# Acondicionamiento_70Q.net
KiCad netlist of a schematic drawn in Altium Designer
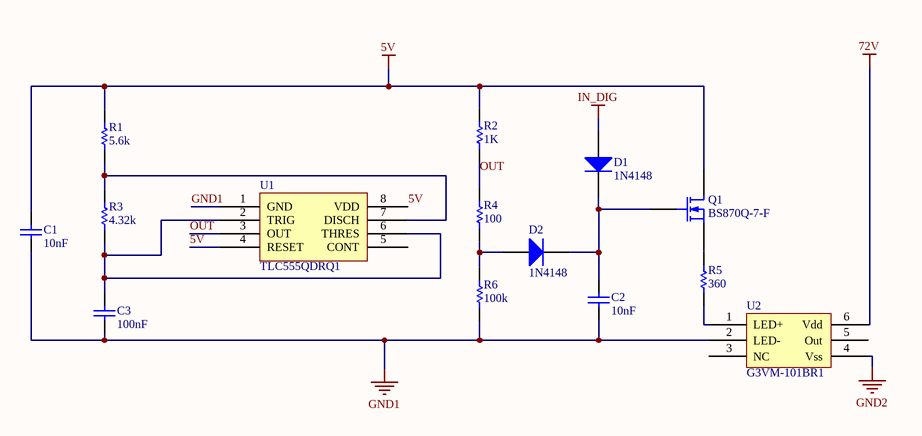
[diagram p0: Acondicionamiento_70Q.SchDoc]

(export (version "E")
  (design (tool "Eeschema 10.0.6"))
  (components
    (comp (ref "C1")
      (value "10nF")
      (footprint "C0805")
      (description "C0805C103K5RACTU - CAP, 0.01µF, 50V, 10%, X7R, 0805, REEL")
      (fields
        (field (name "MANUFACTURER") "KEMET")
        (field (name "MANUFACTURER PART NUMBER") "C0805C103K5RACTU")
      )
      (libsource (lib "Metro PA-M50") (part "CAP-10nF/50V"))
    )
    (comp (ref "C2")
      (value "10nF")
      (footprint "C0805")
      (description "C0805C103K5RACTU - CAP, 0.01µF, 50V, 10%, X7R, 0805, REEL")
      (fields
        (field (name "MANUFACTURER") "KEMET")
        (field (name "MANUFACTURER PART NUMBER") "C0805C103K5RACTU")
      )
      (libsource (lib "Metro PA-M50") (part "CAP-10nF/50V"))
    )
    (comp (ref "C3")
      (value "100nF")
      (footprint "C0805_B")
      (description "CC0805JPX7R8BB104")
      (fields
        (field (name "MANUFACTURER") "Yageo")
        (field (name "MANUFACTURER PART NUMBER") "CC1206JKX7R9BB105")
        (field (name "PUBLISHER") "Altium Limited")
      )
      (libsource (lib "Metro PA-M50") (part "CAP-0.1uF_0805_B"))
    )
    (comp (ref "D1")
      (value "1N4148")
      (footprint "SOD-323-2")
      (description "1N4148WS-HG3-08")
      (fields (field (name "MANUFACTURER") "Vishay Semiconductors"))
      (libsource (lib "Metro PA-M50") (part "DIO-1N4148"))
    )
    (comp (ref "D2")
      (value "1N4148")
      (footprint "SOD-323-2")
      (description "1N4148WS-HG3-08")
      (fields (field (name "MANUFACTURER") "Vishay Semiconductors"))
      (libsource (lib "Metro PA-M50") (part "DIO-1N4148"))
    )
    (comp (ref "Q1")
      (value "BS870Q-7-F")
      (footprint "SOT23_3")
      (description "MOSFET CHANNEL N 41V 60V SOT23")
      (fields (field (name "MANUFACTURER") "Diodes"))
      (libsource (lib "Metro PA-M50") (part "MOS_N-BS870Q-7-F"))
    )
    (comp (ref "R1")
      (value "5.6k")
      (footprint "R-0805")
      (description "PCF0805-13-5K6BT1 WELWYN  THIN FILM RESISTOR, 5.6KOHM, 100mW 0.1%")
      (fields
        (field (name "MANUFACTURER") "TT Welwyn")
        (field (name "MANUFACTURER PART NUMBER") "PCF0805-13-5K6-B-T1")
      )
      (libsource (lib "Metro PA-M50") (part "RES-5.6K/0805"))
    )
    (comp (ref "R2")
      (value "1K")
      (footprint "R-0805")
      (description "Thin Film Resistors - SMD 1Kohms .1% 25ppm")
      (fields
        (field (name "MANUFACTURER") "Vishay Sfernice")
        (field (name "MANUFACTURER PART NUMBER") "P-0805E1001BBT1")
      )
      (libsource (lib "Metro PA-M50") (part "RES-1K/0805"))
    )
    (comp (ref "R3")
      (value "4.32k")
      (footprint "R-0805")
      (description "ERA-6AEB4321V")
      (fields (field (name "TOLERANCE") "0.1%") (field (name "MANUFACTURER") "Panasonic"))
      (libsource (lib "Metro PA-M50") (part "Res-4.32k"))
    )
    (comp (ref "R4")
      (value "100")
      (footprint "R-0805")
      (description "MCU08050C1000FP500")
      (fields (field (name "MANUFACTURER") "Vishay Beyschlag") (field (name "TOLERANCE") "1%"))
      (libsource (lib "Metro PA-M50") (part "RES-100"))
    )
    (comp (ref "R5")
      (value "360")
      (footprint "R-0805")
      (description "ERJ-6ENF3600V            RESISTOR, THICK FILM, 360OHM, 125mW, ± 1%")
      (fields
        (field (name "MANUFACTURER") "Panasonic")
        (field (name "MANUFACTURER PART NUMBER") "ERJ-6ENF3600V")
      )
      (libsource (lib "Metro PA-M50") (part "RES-360"))
    )
    (comp (ref "R6")
      (value "100k")
      (footprint "R-0805")
      (description "TNPW0805100KBEEA Res Thick Film 1206 100K Ohm 1% 0.25W(1/4W) ±100ppm/C Pad SMD T/R")
      (fields
        (field (name "MANUFACTURER") "Vishay Dale")
        (field (name "MANUFACTURER PART NUMBER") "TNPW0805100KBEEA")
      )
      (libsource (lib "Metro PA-M50") (part "RES-100k/0805"))
    )
    (comp (ref "U1")
      (value "TLC555QDRQ1")
      (footprint "SOIC8")
      (description "Standard Timer Single Automotive 8-Pin SOIC T/R")
      (fields (field (name "MANUFACTURER") "Texas Instruments"))
      (libsource (lib "Metro PA-M50") (part "Timer-TLC555-Q1"))
    )
    (comp (ref "U2")
      (value "G3VM-101BR1")
      (footprint "DIP-6")
      (description "G3VM-101BR1 Mosfet Relay SPST 4A 6DIP")
      (fields (field (name "MANUFACTURER") "Omron"))
      (libsource (lib "Metro PA-M50") (part "Optoacoplador-G3VM-101BR1"))
    )
  )
  (nets
    (net (code "1") (name "/OUT") (class "Default")
      (node (ref "R2") (pin "1") (pinfunction "1_1") (pintype "passive"))
      (node (ref "R4") (pin "2") (pinfunction "2_2") (pintype "passive"))
      (node (ref "U1") (pin "3") (pinfunction "OUT_3") (pintype "passive"))
    )
    (net (code "2") (name "5V") (class "Default")
      (node (ref "C1") (pin "2") (pinfunction "2_2") (pintype "passive"))
      (node (ref "Q1") (pin "3") (pinfunction "D_3") (pintype "passive"))
      (node (ref "R1") (pin "2") (pinfunction "2_2") (pintype "passive"))
      (node (ref "R2") (pin "2") (pinfunction "2_2") (pintype "passive"))
      (node (ref "U1") (pin "4") (pinfunction "RESET_4") (pintype "passive"))
      (node (ref "U1") (pin "8") (pinfunction "VDD_8") (pintype "passive"))
    )
    (net (code "3") (name "72V") (class "Default")
      (node (ref "U2") (pin "6") (pinfunction "Vdd_6") (pintype "passive"))
    )
    (net (code "4") (name "GND1") (class "Default")
      (node (ref "C1") (pin "1") (pinfunction "1_1") (pintype "passive"))
      (node (ref "C2") (pin "1") (pinfunction "1_1") (pintype "passive"))
      (node (ref "C3") (pin "1") (pinfunction "1_1") (pintype "passive"))
      (node (ref "R6") (pin "1") (pinfunction "1_1") (pintype "passive"))
      (node (ref "U1") (pin "1") (pinfunction "GND_1") (pintype "passive"))
      (node (ref "U2") (pin "2") (pinfunction "LED-_2") (pintype "passive"))
    )
    (net (code "5") (name "GND2") (class "Default")
      (node (ref "U2") (pin "4") (pinfunction "Vss_4") (pintype "passive"))
    )
    (net (code "6") (name "IN_DIG") (class "Default")
      (node (ref "D1") (pin "1") (pinfunction "A_1") (pintype "passive"))
    )
    (net (code "7") (name "Net-(D1-K)") (class "Default")
      (node (ref "C2") (pin "2") (pinfunction "2_2") (pintype "passive"))
      (node (ref "D1") (pin "2") (pinfunction "K_2") (pintype "passive"))
      (node (ref "D2") (pin "2") (pinfunction "K_2") (pintype "passive"))
      (node (ref "Q1") (pin "1") (pinfunction "G_1") (pintype "passive"))
    )
    (net (code "8") (name "Net-(D2-A)") (class "Default")
      (node (ref "D2") (pin "1") (pinfunction "A_1") (pintype "passive"))
      (node (ref "R4") (pin "1") (pinfunction "1_1") (pintype "passive"))
      (node (ref "R6") (pin "2") (pinfunction "2_2") (pintype "passive"))
    )
    (net (code "9") (name "Net-(Q1-S)") (class "Default")
      (node (ref "Q1") (pin "2") (pinfunction "S_2") (pintype "passive"))
      (node (ref "R5") (pin "2") (pinfunction "2_2") (pintype "passive"))
    )
    (net (code "10") (name "Net-(U1-DISCH)") (class "Default")
      (node (ref "R1") (pin "1") (pinfunction "1_1") (pintype "passive"))
      (node (ref "R3") (pin "2") (pinfunction "2_2") (pintype "passive"))
      (node (ref "U1") (pin "7") (pinfunction "DISCH_7") (pintype "passive"))
    )
    (net (code "11") (name "Net-(U1-THRES)") (class "Default")
      (node (ref "C3") (pin "2") (pinfunction "2_2") (pintype "passive"))
      (node (ref "R3") (pin "1") (pinfunction "1_1") (pintype "passive"))
      (node (ref "U1") (pin "2") (pinfunction "TRIG_2") (pintype "passive"))
      (node (ref "U1") (pin "6") (pinfunction "THRES_6") (pintype "passive"))
    )
    (net (code "12") (name "Net-(U2-LED+)") (class "Default")
      (node (ref "R5") (pin "1") (pinfunction "1_1") (pintype "passive"))
      (node (ref "U2") (pin "1") (pinfunction "LED+_1") (pintype "passive"))
    )
    (net (code "13") (name "unconnected-(U1-CONT-Pad5)") (class "Default")
      (node (ref "U1") (pin "5") (pinfunction "CONT_5") (pintype "passive"))
    )
    (net (code "14") (name "unconnected-(U2-NC-Pad3)") (class "Default")
      (node (ref "U2") (pin "3") (pinfunction "NC_3") (pintype "passive"))
    )
    (net (code "15") (name "unconnected-(U2-Out-Pad5)") (class "Default")
      (node (ref "U2") (pin "5") (pinfunction "Out_5") (pintype "passive"))
    )
  )
)
